# 4_Shutdown.net
KiCad netlist of a schematic drawn in Altium Designer
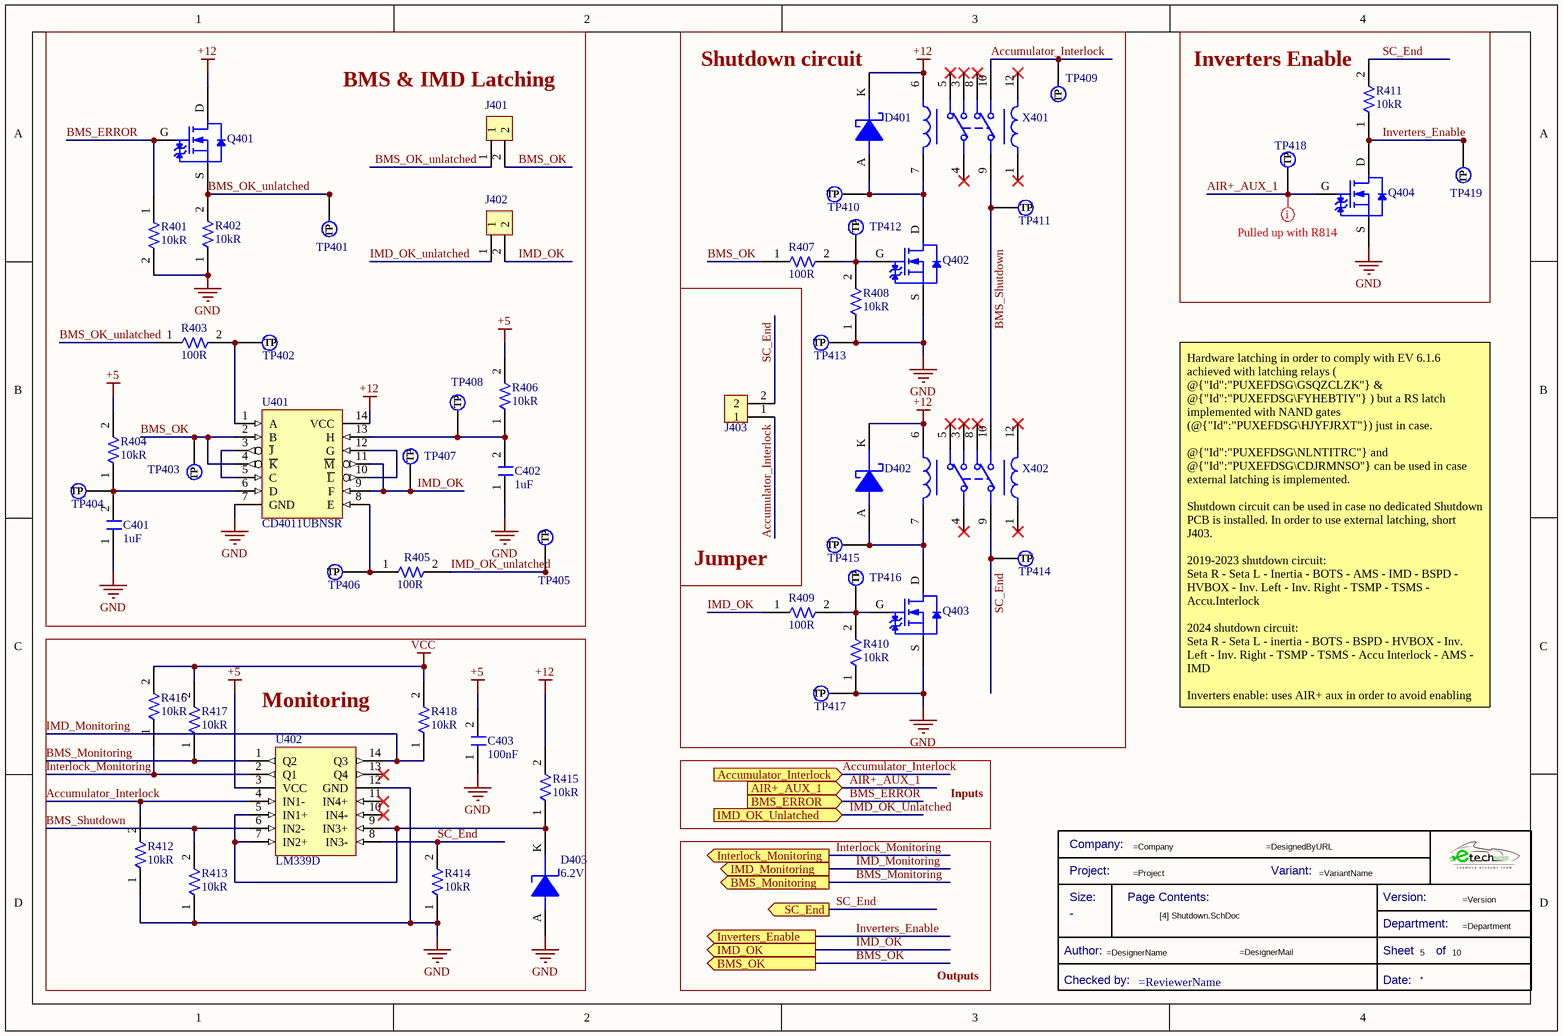
[diagram p0: [4] Shutdown.SchDoc]

(export (version "E")
  (design (tool "Eeschema 10.0.6"))
  (components
    (comp (ref "*")
      (value "Title Block_template")
      (description "Standard Title Block")
      (fields (field (name "SIZE") "-"))
      (libsource (lib "e-Tech_Racing") (part "Title Block_template"))
    )
    (comp (ref "C401")
      (value "885012207103")
      (footprint "C0805FNPC-R")
      (fields
        (field (name "TOLERANCE") "10%")
        (field (name "CAPACITANCE") "1uF")
        (field (name ".CREATOR") "GP")
      )
      (libsource (lib "Passives") (part "C1u-50V-0805FNPC-X7R"))
    )
    (comp (ref "C402")
      (value "885012207103")
      (footprint "C0805FNPC-R")
      (fields
        (field (name "TOLERANCE") "10%")
        (field (name "CAPACITANCE") "1uF")
        (field (name ".CREATOR") "GP")
      )
      (libsource (lib "Passives") (part "C1u-50V-0805FNPC-X7R"))
    )
    (comp (ref "C403")
      (value "885012207098")
      (footprint "C0805FNPC-R")
      (description "Cap, 0.1ΜF, 50V, 10%, X7R, 0805")
      (fields
        (field (name "TOLERANCE") "10%")
        (field (name "CAPACITANCE") "100nF")
        (field (name ".CREATOR") "DR")
      )
      (libsource (lib "Passives") (part "C100n-50V-0805FNPC-X7R"))
    )
    (comp (ref "D401")
      (value "MBR0530")
      (footprint "DSC-SOD123")
      (description "VR=30V IF=500mA 30pF P=410mW")
      (fields (field (name ".CREATOR") "GP"))
      (libsource (lib "Filter components") (part "DSC-0.5/30-SOD123"))
    )
    (comp (ref "D402")
      (value "MBR0530")
      (footprint "DSC-SOD123")
      (description "VR=30V IF=500mA 30pF P=410mW")
      (fields (field (name ".CREATOR") "GP"))
      (libsource (lib "Filter components") (part "DSC-0.5/30-SOD123"))
    )
    (comp (ref "D403")
      (value "BZG05C6V2-E3-TR")
      (footprint "DZ-6.2V-DO-214AC")
      (description "BZG05C Series 6.2 V 200 mA Surface Mount Zener Diode - DO-214AC")
      (fields
        (field (name "TOLERANCE") "5%")
        (field (name "ZENER VOLTAGE") "6.2V")
        (field (name ".CREATOR") "DO")
      )
      (libsource (lib "Semiconductor") (part "DZ-6.2V-DO-214AC"))
    )
    (comp (ref "J401")
      (value "61300211121")
      (footprint "J_Pinheader_1x2")
      (description "CONN HEADER 2 POS 2.54")
      (fields (field (name "MANUFACTURER") "Molex") (field (name ".CREATOR") "GP"))
      (libsource (lib "Electromechanical") (part "J_Jumper"))
    )
    (comp (ref "J402")
      (value "61300211121")
      (footprint "J_Pinheader_1x2")
      (description "CONN HEADER 2 POS 2.54")
      (fields (field (name "MANUFACTURER") "Molex") (field (name ".CREATOR") "GP"))
      (libsource (lib "Electromechanical") (part "J_Jumper"))
    )
    (comp (ref "J403")
      (value "61300211121")
      (footprint "J_Pinheader_1x2")
      (description "CONN HEADER 2 POS 2.54")
      (fields (field (name "MANUFACTURER") "Molex") (field (name ".CREATOR") "GP"))
      (libsource (lib "") (part "J_Jumper_1"))
    )
    (comp (ref "Q401")
      (value "CPH3455-TL-H")
      (footprint "TRT-NCH-3/35-CPH")
      (description "CPH3455-TL-H N-channel MOSFET Transistor; 3 A; 35 V; 3-Pin CPH")
      (fields (field (name "MANUFACTURER") "ON Semiconductor") (field (name ".CREATOR") "GP"))
      (libsource (lib "Semiconductor") (part "TRT-NCH-3/35-CPH"))
    )
    (comp (ref "Q402")
      (value "CPH3455-TL-H")
      (footprint "TRT-NCH-3/35-CPH")
      (description "CPH3455-TL-H N-channel MOSFET Transistor; 3 A; 35 V; 3-Pin CPH")
      (fields (field (name "MANUFACTURER") "ON Semiconductor") (field (name ".CREATOR") "GP"))
      (libsource (lib "Semiconductor") (part "TRT-NCH-3/35-CPH"))
    )
    (comp (ref "Q403")
      (value "CPH3455-TL-H")
      (footprint "TRT-NCH-3/35-CPH")
      (description "CPH3455-TL-H N-channel MOSFET Transistor; 3 A; 35 V; 3-Pin CPH")
      (fields (field (name "MANUFACTURER") "ON Semiconductor") (field (name ".CREATOR") "GP"))
      (libsource (lib "Semiconductor") (part "TRT-NCH-3/35-CPH"))
    )
    (comp (ref "Q404")
      (value "CPH3455-TL-H")
      (footprint "TRT-NCH-3/35-CPH")
      (description "CPH3455-TL-H N-channel MOSFET Transistor; 3 A; 35 V; 3-Pin CPH")
      (fields (field (name "MANUFACTURER") "ON Semiconductor") (field (name ".CREATOR") "GP"))
      (libsource (lib "Semiconductor") (part "TRT-NCH-3/35-CPH"))
    )
    (comp (ref "R401")
      (value "CR0805-JW-103ELF")
      (footprint "R0805FTK")
      (fields
        (field (name "TOLERANCE") "5%")
        (field (name "RESISTANCE") "10kR")
        (field (name ".CREATOR") "DR")
      )
      (libsource (lib "Passives") (part "R10k-0805FTK"))
    )
    (comp (ref "R402")
      (value "CR0805-JW-103ELF")
      (footprint "R0805FTK")
      (fields
        (field (name "TOLERANCE") "5%")
        (field (name "RESISTANCE") "10kR")
        (field (name ".CREATOR") "DR")
      )
      (libsource (lib "Passives") (part "R10k-0805FTK"))
    )
    (comp (ref "R403")
      (value "CR0805-FX-1000ELF")
      (footprint "R0805FTK")
      (description "Res Thick Film 0805 100 Ohm 1% 1/8W ±100ppm/°C Molded SMD SMD Paper Tape on Plastic Reel")
      (fields
        (field (name "TOLERANCE") "1%")
        (field (name "RESISTANCE") "100R")
        (field (name ".CREATOR") "DR")
      )
      (libsource (lib "Passives") (part "R100-0805FTK"))
    )
    (comp (ref "R404")
      (value "CR0805-JW-103ELF")
      (footprint "R0805FTK")
      (fields
        (field (name "TOLERANCE") "5%")
        (field (name "RESISTANCE") "10kR")
        (field (name ".CREATOR") "DR")
      )
      (libsource (lib "Passives") (part "R10k-0805FTK"))
    )
    (comp (ref "R405")
      (value "CR0805-FX-1000ELF")
      (footprint "R0805FTK")
      (description "Res Thick Film 0805 100 Ohm 1% 1/8W ±100ppm/°C Molded SMD SMD Paper Tape on Plastic Reel")
      (fields
        (field (name "TOLERANCE") "1%")
        (field (name "RESISTANCE") "100R")
        (field (name ".CREATOR") "DR")
      )
      (libsource (lib "Passives") (part "R100-0805FTK"))
    )
    (comp (ref "R406")
      (value "CR0805-JW-103ELF")
      (footprint "R0805FTK")
      (fields
        (field (name "TOLERANCE") "5%")
        (field (name "RESISTANCE") "10kR")
        (field (name ".CREATOR") "DR")
      )
      (libsource (lib "Passives") (part "R10k-0805FTK"))
    )
    (comp (ref "R407")
      (value "CR0805-FX-1000ELF")
      (footprint "R0805FTK")
      (description "Res Thick Film 0805 100 Ohm 1% 1/8W ±100ppm/°C Molded SMD SMD Paper Tape on Plastic Reel")
      (fields
        (field (name "TOLERANCE") "1%")
        (field (name "RESISTANCE") "100R")
        (field (name ".CREATOR") "DR")
      )
      (libsource (lib "Passives") (part "R100-0805FTK"))
    )
    (comp (ref "R408")
      (value "CR0805-JW-103ELF")
      (footprint "R0805FTK")
      (fields
        (field (name "TOLERANCE") "5%")
        (field (name "RESISTANCE") "10kR")
        (field (name ".CREATOR") "DR")
      )
      (libsource (lib "Passives") (part "R10k-0805FTK"))
    )
    (comp (ref "R409")
      (value "CR0805-FX-1000ELF")
      (footprint "R0805FTK")
      (description "Res Thick Film 0805 100 Ohm 1% 1/8W ±100ppm/°C Molded SMD SMD Paper Tape on Plastic Reel")
      (fields
        (field (name "TOLERANCE") "1%")
        (field (name "RESISTANCE") "100R")
        (field (name ".CREATOR") "DR")
      )
      (libsource (lib "Passives") (part "R100-0805FTK"))
    )
    (comp (ref "R410")
      (value "CR0805-JW-103ELF")
      (footprint "R0805FTK")
      (fields
        (field (name "TOLERANCE") "5%")
        (field (name "RESISTANCE") "10kR")
        (field (name ".CREATOR") "DR")
      )
      (libsource (lib "Passives") (part "R10k-0805FTK"))
    )
    (comp (ref "R411")
      (value "CR0805-JW-103ELF")
      (footprint "R0805FTK")
      (fields
        (field (name "TOLERANCE") "5%")
        (field (name "RESISTANCE") "10kR")
        (field (name ".CREATOR") "DR")
      )
      (libsource (lib "Passives") (part "R10k-0805FTK"))
    )
    (comp (ref "R412")
      (value "CR0805-JW-103ELF")
      (footprint "R0805FTK")
      (fields
        (field (name "TOLERANCE") "5%")
        (field (name "RESISTANCE") "10kR")
        (field (name ".CREATOR") "DR")
      )
      (libsource (lib "Passives") (part "R10k-0805FTK"))
    )
    (comp (ref "R413")
      (value "CR0805-JW-103ELF")
      (footprint "R0805FTK")
      (fields
        (field (name "TOLERANCE") "5%")
        (field (name "RESISTANCE") "10kR")
        (field (name ".CREATOR") "DR")
      )
      (libsource (lib "Passives") (part "R10k-0805FTK"))
    )
    (comp (ref "R414")
      (value "CR0805-JW-103ELF")
      (footprint "R0805FTK")
      (fields
        (field (name "TOLERANCE") "5%")
        (field (name "RESISTANCE") "10kR")
        (field (name ".CREATOR") "DR")
      )
      (libsource (lib "Passives") (part "R10k-0805FTK"))
    )
    (comp (ref "R415")
      (value "CR0805-JW-103ELF")
      (footprint "R0805FTK")
      (fields
        (field (name "TOLERANCE") "5%")
        (field (name "RESISTANCE") "10kR")
        (field (name ".CREATOR") "DR")
      )
      (libsource (lib "Passives") (part "R10k-0805FTK"))
    )
    (comp (ref "R416")
      (value "CR0805-JW-103ELF")
      (footprint "R0805FTK")
      (fields
        (field (name "TOLERANCE") "5%")
        (field (name "RESISTANCE") "10kR")
        (field (name ".CREATOR") "DR")
      )
      (libsource (lib "Passives") (part "R10k-0805FTK"))
    )
    (comp (ref "R417")
      (value "CR0805-JW-103ELF")
      (footprint "R0805FTK")
      (fields
        (field (name "TOLERANCE") "5%")
        (field (name "RESISTANCE") "10kR")
        (field (name ".CREATOR") "DR")
      )
      (libsource (lib "Passives") (part "R10k-0805FTK"))
    )
    (comp (ref "R418")
      (value "CR0805-JW-103ELF")
      (footprint "R0805FTK")
      (fields
        (field (name "TOLERANCE") "5%")
        (field (name "RESISTANCE") "10kR")
        (field (name ".CREATOR") "DR")
      )
      (libsource (lib "Passives") (part "R10k-0805FTK"))
    )
    (comp (ref "TP401")
      (value "TestPoint")
      (footprint "TestPoint")
      (description "Test Point 1x1 mm")
      (fields (field (name ".CREATOR") "GP") (field (name ".PCBCHECK") "GP") (field (name ".SCHCHECK") "GP"))
      (libsource (lib "e-Tech_Racing") (part "TestPoint"))
    )
    (comp (ref "TP402")
      (value "TestPoint")
      (footprint "TestPoint")
      (description "Test Point 1x1 mm")
      (fields (field (name ".CREATOR") "GP") (field (name ".PCBCHECK") "GP") (field (name ".SCHCHECK") "GP"))
      (libsource (lib "e-Tech_Racing") (part "TestPoint"))
    )
    (comp (ref "TP403")
      (value "TestPoint")
      (footprint "TestPoint")
      (description "Test Point 1x1 mm")
      (fields (field (name ".CREATOR") "GP") (field (name ".PCBCHECK") "GP") (field (name ".SCHCHECK") "GP"))
      (libsource (lib "e-Tech_Racing") (part "TestPoint"))
    )
    (comp (ref "TP404")
      (value "TestPoint")
      (footprint "TestPoint")
      (description "Test Point 1x1 mm")
      (fields (field (name ".CREATOR") "GP") (field (name ".PCBCHECK") "GP") (field (name ".SCHCHECK") "GP"))
      (libsource (lib "e-Tech_Racing") (part "TestPoint"))
    )
    (comp (ref "TP405")
      (value "TestPoint")
      (footprint "TestPoint")
      (description "Test Point 1x1 mm")
      (fields (field (name ".CREATOR") "GP") (field (name ".PCBCHECK") "GP") (field (name ".SCHCHECK") "GP"))
      (libsource (lib "e-Tech_Racing") (part "TestPoint"))
    )
    (comp (ref "TP406")
      (value "TestPoint")
      (footprint "TestPoint")
      (description "Test Point 1x1 mm")
      (fields (field (name ".CREATOR") "GP") (field (name ".PCBCHECK") "GP") (field (name ".SCHCHECK") "GP"))
      (libsource (lib "e-Tech_Racing") (part "TestPoint"))
    )
    (comp (ref "TP407")
      (value "TestPoint")
      (footprint "TestPoint")
      (description "Test Point 1x1 mm")
      (fields (field (name ".CREATOR") "GP") (field (name ".PCBCHECK") "GP") (field (name ".SCHCHECK") "GP"))
      (libsource (lib "e-Tech_Racing") (part "TestPoint"))
    )
    (comp (ref "TP408")
      (value "TestPoint")
      (footprint "TestPoint")
      (description "Test Point 1x1 mm")
      (fields (field (name ".CREATOR") "GP") (field (name ".PCBCHECK") "GP") (field (name ".SCHCHECK") "GP"))
      (libsource (lib "e-Tech_Racing") (part "TestPoint"))
    )
    (comp (ref "TP409")
      (value "TestPoint")
      (footprint "TestPoint")
      (description "Test Point 1x1 mm")
      (fields (field (name ".CREATOR") "GP") (field (name ".PCBCHECK") "GP") (field (name ".SCHCHECK") "GP"))
      (libsource (lib "e-Tech_Racing") (part "TestPoint"))
    )
    (comp (ref "TP410")
      (value "TestPoint")
      (footprint "TestPoint")
      (description "Test Point 1x1 mm")
      (fields (field (name ".CREATOR") "GP") (field (name ".PCBCHECK") "GP") (field (name ".SCHCHECK") "GP"))
      (libsource (lib "e-Tech_Racing") (part "TestPoint"))
    )
    (comp (ref "TP411")
      (value "TestPoint")
      (footprint "TestPoint")
      (description "Test Point 1x1 mm")
      (fields (field (name ".CREATOR") "GP") (field (name ".PCBCHECK") "GP") (field (name ".SCHCHECK") "GP"))
      (libsource (lib "e-Tech_Racing") (part "TestPoint"))
    )
    (comp (ref "TP412")
      (value "TestPoint")
      (footprint "TestPoint")
      (description "Test Point 1x1 mm")
      (fields (field (name ".CREATOR") "GP") (field (name ".PCBCHECK") "GP") (field (name ".SCHCHECK") "GP"))
      (libsource (lib "e-Tech_Racing") (part "TestPoint"))
    )
    (comp (ref "TP413")
      (value "TestPoint")
      (footprint "TestPoint")
      (description "Test Point 1x1 mm")
      (fields (field (name ".CREATOR") "GP") (field (name ".PCBCHECK") "GP") (field (name ".SCHCHECK") "GP"))
      (libsource (lib "e-Tech_Racing") (part "TestPoint"))
    )
    (comp (ref "TP414")
      (value "TestPoint")
      (footprint "TestPoint")
      (description "Test Point 1x1 mm")
      (fields (field (name ".CREATOR") "GP") (field (name ".PCBCHECK") "GP") (field (name ".SCHCHECK") "GP"))
      (libsource (lib "e-Tech_Racing") (part "TestPoint"))
    )
    (comp (ref "TP415")
      (value "TestPoint")
      (footprint "TestPoint")
      (description "Test Point 1x1 mm")
      (fields (field (name ".CREATOR") "GP") (field (name ".PCBCHECK") "GP") (field (name ".SCHCHECK") "GP"))
      (libsource (lib "e-Tech_Racing") (part "TestPoint"))
    )
    (comp (ref "TP416")
      (value "TestPoint")
      (footprint "TestPoint")
      (description "Test Point 1x1 mm")
      (fields (field (name ".CREATOR") "GP") (field (name ".PCBCHECK") "GP") (field (name ".SCHCHECK") "GP"))
      (libsource (lib "e-Tech_Racing") (part "TestPoint"))
    )
    (comp (ref "TP417")
      (value "TestPoint")
      (footprint "TestPoint")
      (description "Test Point 1x1 mm")
      (fields (field (name ".CREATOR") "GP") (field (name ".PCBCHECK") "GP") (field (name ".SCHCHECK") "GP"))
      (libsource (lib "e-Tech_Racing") (part "TestPoint"))
    )
    (comp (ref "TP418")
      (value "TestPoint")
      (footprint "TestPoint")
      (description "Test Point 1x1 mm")
      (fields (field (name ".CREATOR") "GP") (field (name ".PCBCHECK") "GP") (field (name ".SCHCHECK") "GP"))
      (libsource (lib "e-Tech_Racing") (part "TestPoint"))
    )
    (comp (ref "TP419")
      (value "TestPoint")
      (footprint "TestPoint")
      (description "Test Point 1x1 mm")
      (fields (field (name ".CREATOR") "GP") (field (name ".PCBCHECK") "GP") (field (name ".SCHCHECK") "GP"))
      (libsource (lib "e-Tech_Racing") (part "TestPoint"))
    )
    (comp (ref "U401")
      (value "CD4011UBSNR")
      (footprint "ARRAY_4_NAND")
      (description "CD4011UB Cmos Quad 2-INPUT Nand")
      (fields
        (field (name "MANUFACTURER") "Texas Instruments")
        (field (name "MANUFACTURER PART NUMBER") "CD4011UBNSR")
        (field (name ".CREATOR") "DO")
      )
      (libsource (lib "Integrated circuits") (part "Array_4_NAND"))
    )
    (comp (ref "U402")
      (value "LM339D")
      (footprint "Array_4_Amp_LM339D")
      (description "Comparator Quad ±18V/36V 14-Pin SOIC Tube")
      (fields
        (field (name "MANUFACTURER") "Texas Instruments")
        (field (name "MANUFACTURER PART NUMBER") "LM339D")
        (field (name ".CREATOR") "DO")
      )
      (libsource (lib "Integrated circuits") (part "Array_4_Amp_LM339D"))
    )
    (comp (ref "X401")
      (value "Relay_V23079")
      (footprint "Relay_V23079")
      (description "Electromechanical Relay 5VDC 178Ohm 2A DPDT (14.5x7.2x9.8)mm THT Signal Relay")
      (libsource (lib "Electromechanical") (part "Relay_V23079"))
    )
    (comp (ref "X402")
      (value "Relay_V23079")
      (footprint "Relay_V23079")
      (description "Electromechanical Relay 5VDC 178Ohm 2A DPDT (14.5x7.2x9.8)mm THT Signal Relay")
      (libsource (lib "Electromechanical") (part "Relay_V23079"))
    )
  )
  (nets
    (net (code "1") (name "+5") (class "Default")
      (node (ref "C403") (pin "2") (pinfunction "2_2") (pintype "passive"))
      (node (ref "R404") (pin "2") (pinfunction "2_2") (pintype "passive"))
      (node (ref "R406") (pin "2") (pinfunction "2_2") (pintype "passive"))
      (node (ref "U402") (pin "3") (pinfunction "VCC_3") (pintype "power_in"))
    )
    (net (code "2") (name "+12") (class "Default")
      (node (ref "D401") (pin "K") (pinfunction "K_K") (pintype "passive"))
      (node (ref "D402") (pin "K") (pinfunction "K_K") (pintype "passive"))
      (node (ref "Q401") (pin "D") (pinfunction "D_D") (pintype "passive"))
      (node (ref "R415") (pin "2") (pinfunction "2_2") (pintype "passive"))
      (node (ref "U401") (pin "14") (pinfunction "VCC_14") (pintype "power_in"))
      (node (ref "X401") (pin "6") (pinfunction "6_6") (pintype "passive"))
      (node (ref "X402") (pin "6") (pinfunction "6_6") (pintype "passive"))
    )
    (net (code "3") (name "/AIR+_AUX_1") (class "Default")
      (node (ref "Q404") (pin "G") (pinfunction "G_G") (pintype "passive"))
      (node (ref "TP418") (pin "1") (pinfunction "TP_1") (pintype "passive"))
    )
    (net (code "4") (name "/Accumulator_Interlock") (class "Default")
      (node (ref "J403") (pin "1") (pinfunction "1_1") (pintype "passive"))
      (node (ref "R412") (pin "2") (pinfunction "2_2") (pintype "passive"))
      (node (ref "TP409") (pin "1") (pinfunction "TP_1") (pintype "passive"))
      (node (ref "U402") (pin "4") (pinfunction "IN1-_4") (pintype "input"))
      (node (ref "X401") (pin "10") (pinfunction "10_10") (pintype "passive"))
    )
    (net (code "5") (name "/BMS_ERROR") (class "Default")
      (node (ref "Q401") (pin "G") (pinfunction "G_G") (pintype "passive"))
      (node (ref "R401") (pin "1") (pinfunction "1_1") (pintype "passive"))
    )
    (net (code "6") (name "/BMS_Monitoring") (class "Default")
      (node (ref "R417") (pin "1") (pinfunction "1_1") (pintype "passive"))
      (node (ref "U402") (pin "1") (pinfunction "Q2_1") (pintype "output"))
    )
    (net (code "7") (name "/BMS_OK") (class "Default")
      (node (ref "J401") (pin "2") (pinfunction "2_2") (pintype "passive"))
      (node (ref "R407") (pin "1") (pinfunction "1_1") (pintype "passive"))
      (node (ref "TP403") (pin "1") (pinfunction "TP_1") (pintype "passive"))
      (node (ref "U401") (pin "2") (pinfunction "B_2") (pintype "input"))
      (node (ref "U401") (pin "4") (pinfunction "~{K}_4") (pintype "output"))
    )
    (net (code "8") (name "/BMS_OK_unlatched") (class "Default")
      (node (ref "J401") (pin "1") (pinfunction "1_1") (pintype "passive"))
      (node (ref "Q401") (pin "S") (pinfunction "S_S") (pintype "passive"))
      (node (ref "R402") (pin "2") (pinfunction "2_2") (pintype "passive"))
      (node (ref "R403") (pin "1") (pinfunction "1_1") (pintype "passive"))
      (node (ref "TP401") (pin "1") (pinfunction "TP_1") (pintype "passive"))
    )
    (net (code "9") (name "/BMS_Shutdown") (class "Default")
      (node (ref "R413") (pin "2") (pinfunction "2_2") (pintype "passive"))
      (node (ref "TP411") (pin "1") (pinfunction "TP_1") (pintype "passive"))
      (node (ref "U402") (pin "6") (pinfunction "IN2-_6") (pintype "input"))
      (node (ref "X401") (pin "9") (pinfunction "9_9") (pintype "passive"))
      (node (ref "X402") (pin "10") (pinfunction "10_10") (pintype "passive"))
    )
    (net (code "10") (name "/IMD_Monitoring") (class "Default")
      (node (ref "R418") (pin "1") (pinfunction "1_1") (pintype "passive"))
      (node (ref "U402") (pin "14") (pinfunction "Q3_14") (pintype "output"))
    )
    (net (code "11") (name "/IMD_OK") (class "Default")
      (node (ref "J402") (pin "2") (pinfunction "2_2") (pintype "passive"))
      (node (ref "R409") (pin "1") (pinfunction "1_1") (pintype "passive"))
      (node (ref "TP407") (pin "1") (pinfunction "TP_1") (pintype "passive"))
      (node (ref "U401") (pin "11") (pinfunction "~{M}_11") (pintype "output"))
      (node (ref "U401") (pin "9") (pinfunction "F_9") (pintype "input"))
    )
    (net (code "13") (name "/IMD_OK_unlatched") (class "Default")
      (node (ref "J402") (pin "1") (pinfunction "1_1") (pintype "passive"))
      (node (ref "R405") (pin "2") (pinfunction "2_2") (pintype "passive"))
      (node (ref "TP405") (pin "1") (pinfunction "TP_1") (pintype "passive"))
    )
    (net (code "14") (name "/Interlock_Monitoring") (class "Default")
      (node (ref "R416") (pin "1") (pinfunction "1_1") (pintype "passive"))
      (node (ref "U402") (pin "2") (pinfunction "Q1_2") (pintype "output"))
    )
    (net (code "15") (name "/Inverters_Enable") (class "Default")
      (node (ref "Q404") (pin "D") (pinfunction "D_D") (pintype "passive"))
      (node (ref "R411") (pin "1") (pinfunction "1_1") (pintype "passive"))
      (node (ref "TP419") (pin "1") (pinfunction "TP_1") (pintype "passive"))
    )
    (net (code "16") (name "/SC_End") (class "Default")
      (node (ref "J403") (pin "2") (pinfunction "2_2") (pintype "passive"))
      (node (ref "R411") (pin "2") (pinfunction "2_2") (pintype "passive"))
      (node (ref "R414") (pin "2") (pinfunction "2_2") (pintype "passive"))
      (node (ref "TP414") (pin "1") (pinfunction "TP_1") (pintype "passive"))
      (node (ref "U402") (pin "8") (pinfunction "IN3-_8") (pintype "input"))
      (node (ref "X402") (pin "9") (pinfunction "9_9") (pintype "passive"))
    )
    (net (code "17") (name "GND") (class "Default")
      (node (ref "C401") (pin "1") (pinfunction "1_1") (pintype "passive"))
      (node (ref "C402") (pin "1") (pinfunction "1_1") (pintype "passive"))
      (node (ref "C403") (pin "1") (pinfunction "1_1") (pintype "passive"))
      (node (ref "D403") (pin "A") (pinfunction "A_A") (pintype "passive"))
      (node (ref "Q402") (pin "S") (pinfunction "S_S") (pintype "passive"))
      (node (ref "Q403") (pin "S") (pinfunction "S_S") (pintype "passive"))
      (node (ref "Q404") (pin "S") (pinfunction "S_S") (pintype "passive"))
      (node (ref "R401") (pin "2") (pinfunction "2_2") (pintype "passive"))
      (node (ref "R402") (pin "1") (pinfunction "1_1") (pintype "passive"))
      (node (ref "R408") (pin "1") (pinfunction "1_1") (pintype "passive"))
      (node (ref "R410") (pin "1") (pinfunction "1_1") (pintype "passive"))
      (node (ref "R412") (pin "1") (pinfunction "1_1") (pintype "passive"))
      (node (ref "R413") (pin "1") (pinfunction "1_1") (pintype "passive"))
      (node (ref "R414") (pin "1") (pinfunction "1_1") (pintype "passive"))
      (node (ref "TP413") (pin "1") (pinfunction "TP_1") (pintype "passive"))
      (node (ref "TP417") (pin "1") (pinfunction "TP_1") (pintype "passive"))
      (node (ref "U401") (pin "7") (pinfunction "GND_7") (pintype "power_in"))
      (node (ref "U402") (pin "12") (pinfunction "GND_12") (pintype "power_in"))
    )
    (net (code "18") (name "Net-(TP402-TP)") (class "Default")
      (node (ref "R403") (pin "2") (pinfunction "2_2") (pintype "passive"))
      (node (ref "TP402") (pin "1") (pinfunction "TP_1") (pintype "passive"))
      (node (ref "U401") (pin "1") (pinfunction "A_1") (pintype "input"))
    )
    (net (code "19") (name "Net-(TP404-TP)") (class "Default")
      (node (ref "C401") (pin "2") (pinfunction "2_2") (pintype "passive"))
      (node (ref "R404") (pin "1") (pinfunction "1_1") (pintype "passive"))
      (node (ref "TP404") (pin "1") (pinfunction "TP_1") (pintype "passive"))
      (node (ref "U401") (pin "6") (pinfunction "D_6") (pintype "input"))
    )
    (net (code "20") (name "Net-(TP406-TP)") (class "Default")
      (node (ref "R405") (pin "1") (pinfunction "1_1") (pintype "passive"))
      (node (ref "TP406") (pin "1") (pinfunction "TP_1") (pintype "passive"))
      (node (ref "U401") (pin "8") (pinfunction "E_8") (pintype "input"))
    )
    (net (code "21") (name "Net-(TP408-TP)") (class "Default")
      (node (ref "C402") (pin "2") (pinfunction "2_2") (pintype "passive"))
      (node (ref "R406") (pin "1") (pinfunction "1_1") (pintype "passive"))
      (node (ref "TP408") (pin "1") (pinfunction "TP_1") (pintype "passive"))
      (node (ref "U401") (pin "13") (pinfunction "H_13") (pintype "input"))
    )
    (net (code "22") (name "Net-(TP410-TP)") (class "Default")
      (node (ref "D401") (pin "A") (pinfunction "A_A") (pintype "passive"))
      (node (ref "Q402") (pin "D") (pinfunction "D_D") (pintype "passive"))
      (node (ref "TP410") (pin "1") (pinfunction "TP_1") (pintype "passive"))
      (node (ref "X401") (pin "7") (pinfunction "7_7") (pintype "passive"))
    )
    (net (code "23") (name "Net-(TP412-TP)") (class "Default")
      (node (ref "Q402") (pin "G") (pinfunction "G_G") (pintype "passive"))
      (node (ref "R407") (pin "2") (pinfunction "2_2") (pintype "passive"))
      (node (ref "R408") (pin "2") (pinfunction "2_2") (pintype "passive"))
      (node (ref "TP412") (pin "1") (pinfunction "TP_1") (pintype "passive"))
    )
    (net (code "24") (name "Net-(TP415-TP)") (class "Default")
      (node (ref "D402") (pin "A") (pinfunction "A_A") (pintype "passive"))
      (node (ref "Q403") (pin "D") (pinfunction "D_D") (pintype "passive"))
      (node (ref "TP415") (pin "1") (pinfunction "TP_1") (pintype "passive"))
      (node (ref "X402") (pin "7") (pinfunction "7_7") (pintype "passive"))
    )
    (net (code "25") (name "Net-(TP416-TP)") (class "Default")
      (node (ref "Q403") (pin "G") (pinfunction "G_G") (pintype "passive"))
      (node (ref "R409") (pin "2") (pinfunction "2_2") (pintype "passive"))
      (node (ref "R410") (pin "2") (pinfunction "2_2") (pintype "passive"))
      (node (ref "TP416") (pin "1") (pinfunction "TP_1") (pintype "passive"))
    )
    (net (code "26") (name "Net-(U401-C)") (class "Default")
      (node (ref "U401") (pin "3") (pinfunction "~{J}_3") (pintype "output"))
      (node (ref "U401") (pin "5") (pinfunction "C_5") (pintype "input"))
    )
    (net (code "27") (name "Net-(U401-G)") (class "Default")
      (node (ref "U401") (pin "10") (pinfunction "~{L}_10") (pintype "output"))
      (node (ref "U401") (pin "12") (pinfunction "G_12") (pintype "input"))
    )
    (net (code "28") (name "Net-(U402-IN1+)") (class "Default")
      (node (ref "D403") (pin "K") (pinfunction "K_K") (pintype "passive"))
      (node (ref "R415") (pin "1") (pinfunction "1_1") (pintype "passive"))
      (node (ref "U402") (pin "5") (pinfunction "IN1+_5") (pintype "input"))
      (node (ref "U402") (pin "7") (pinfunction "IN2+_7") (pintype "input"))
      (node (ref "U402") (pin "9") (pinfunction "IN3+_9") (pintype "input"))
    )
    (net (code "29") (name "VCC") (class "Default")
      (node (ref "R416") (pin "2") (pinfunction "2_2") (pintype "passive"))
      (node (ref "R417") (pin "2") (pinfunction "2_2") (pintype "passive"))
      (node (ref "R418") (pin "2") (pinfunction "2_2") (pintype "passive"))
    )
    (net (code "30") (name "unconnected-(U402-IN4+-Pad11)") (class "Default")
      (node (ref "U402") (pin "11") (pinfunction "IN4+_11") (pintype "input+no_connect"))
    )
    (net (code "31") (name "unconnected-(U402-IN4--Pad10)") (class "Default")
      (node (ref "U402") (pin "10") (pinfunction "IN4-_10") (pintype "input+no_connect"))
    )
    (net (code "32") (name "unconnected-(U402-Q4-Pad13)") (class "Default")
      (node (ref "U402") (pin "13") (pinfunction "Q4_13") (pintype "output+no_connect"))
    )
    (net (code "33") (name "unconnected-(X401-Pad1)") (class "Default")
      (node (ref "X401") (pin "1") (pinfunction "1_1") (pintype "passive+no_connect"))
    )
    (net (code "34") (name "unconnected-(X401-Pad3)") (class "Default")
      (node (ref "X401") (pin "3") (pinfunction "3_3") (pintype "passive+no_connect"))
    )
    (net (code "35") (name "unconnected-(X401-Pad4)") (class "Default")
      (node (ref "X401") (pin "4") (pinfunction "4_4") (pintype "passive+no_connect"))
    )
    (net (code "36") (name "unconnected-(X401-Pad5)") (class "Default")
      (node (ref "X401") (pin "5") (pinfunction "5_5") (pintype "passive+no_connect"))
    )
    (net (code "37") (name "unconnected-(X401-Pad8)") (class "Default")
      (node (ref "X401") (pin "8") (pinfunction "8_8") (pintype "passive+no_connect"))
    )
    (net (code "38") (name "unconnected-(X401-Pad12)") (class "Default")
      (node (ref "X401") (pin "12") (pinfunction "12_12") (pintype "passive+no_connect"))
    )
    (net (code "39") (name "unconnected-(X402-Pad1)") (class "Default")
      (node (ref "X402") (pin "1") (pinfunction "1_1") (pintype "passive+no_connect"))
    )
    (net (code "40") (name "unconnected-(X402-Pad3)") (class "Default")
      (node (ref "X402") (pin "3") (pinfunction "3_3") (pintype "passive+no_connect"))
    )
    (net (code "41") (name "unconnected-(X402-Pad4)") (class "Default")
      (node (ref "X402") (pin "4") (pinfunction "4_4") (pintype "passive+no_connect"))
    )
    (net (code "42") (name "unconnected-(X402-Pad5)") (class "Default")
      (node (ref "X402") (pin "5") (pinfunction "5_5") (pintype "passive+no_connect"))
    )
    (net (code "43") (name "unconnected-(X402-Pad8)") (class "Default")
      (node (ref "X402") (pin "8") (pinfunction "8_8") (pintype "passive+no_connect"))
    )
    (net (code "44") (name "unconnected-(X402-Pad12)") (class "Default")
      (node (ref "X402") (pin "12") (pinfunction "12_12") (pintype "passive+no_connect"))
    )
  )
)
